# Scheme.net
KiCad netlist of a schematic drawn in EAGLE
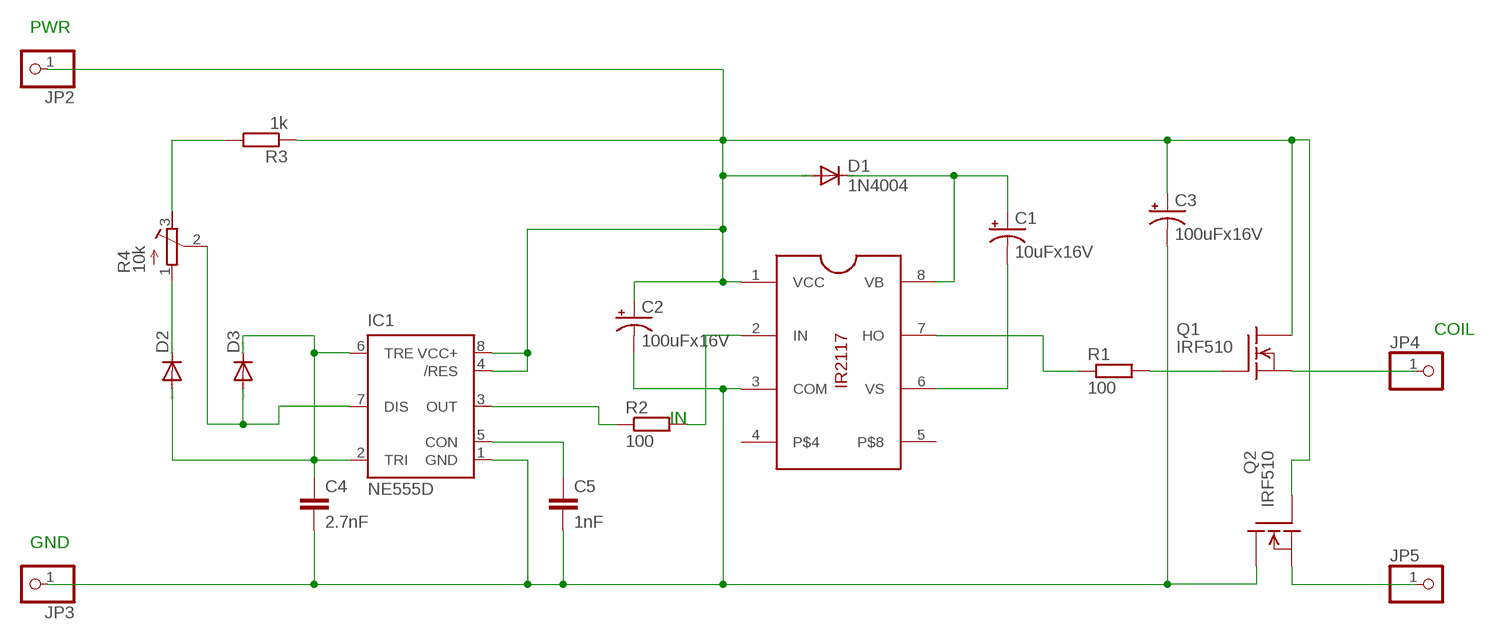
[diagram p0: schematic, sheet 1]

(export (version "E")
  (design (tool "Eeschema 10.0.6"))
  (components
    (comp (ref "C1")
      (value "10uFx16V")
      (footprint "eagle-import:SMC_D")
      (libsource (lib "eagle-import") (part "CPOL-USSMCD"))
    )
    (comp (ref "C2")
      (value "100uFx16V")
      (footprint "eagle-import:SMC_D")
      (libsource (lib "eagle-import") (part "CPOL-USSMCD"))
    )
    (comp (ref "C3")
      (value "100uFx16V")
      (footprint "eagle-import:SMC_D")
      (libsource (lib "eagle-import") (part "CPOL-USSMCD"))
    )
    (comp (ref "C4")
      (value "2.7nF")
      (footprint "eagle-import:C5B4.5")
      (libsource (lib "eagle-import") (part "C5/4.5"))
    )
    (comp (ref "C5")
      (value "1nF")
      (footprint "eagle-import:C5B4.5")
      (libsource (lib "eagle-import") (part "C5/4.5"))
    )
    (comp (ref "D1")
      (value "1N4004")
      (footprint "eagle-import:DO41-10")
      (libsource (lib "eagle-import") (part "1N4004"))
    )
    (comp (ref "D2")
      (value "DIODE-SOD106A-R")
      (footprint "eagle-import:SOD106A-R")
      (libsource (lib "eagle-import") (part "DIODE-SOD106A-R"))
    )
    (comp (ref "D3")
      (value "DIODE-SOD106A-R")
      (footprint "eagle-import:SOD106A-R")
      (libsource (lib "eagle-import") (part "DIODE-SOD106A-R"))
    )
    (comp (ref "IC1")
      (value "NE555D")
      (footprint "eagle-import:SO08")
      (libsource (lib "eagle-import") (part "NE555D"))
    )
    (comp (ref "JP2")
      (value "PINHD-1X1")
      (footprint "eagle-import:1X01")
      (libsource (lib "eagle-import") (part "PINHD-1X1"))
    )
    (comp (ref "JP3")
      (value "PINHD-1X1")
      (footprint "eagle-import:1X01")
      (libsource (lib "eagle-import") (part "PINHD-1X1"))
    )
    (comp (ref "JP4")
      (value "PINHD-1X1")
      (footprint "eagle-import:1X01")
      (libsource (lib "eagle-import") (part "PINHD-1X1"))
    )
    (comp (ref "JP5")
      (value "PINHD-1X1")
      (footprint "eagle-import:1X01")
      (libsource (lib "eagle-import") (part "PINHD-1X1"))
    )
    (comp (ref "Q1")
      (value "IRF510")
      (footprint "eagle-import:TO220")
      (libsource (lib "eagle-import") (part "IRF510"))
    )
    (comp (ref "Q2")
      (value "IRF510")
      (footprint "eagle-import:TO220")
      (libsource (lib "eagle-import") (part "IRF510"))
    )
    (comp (ref "R1")
      (value "100")
      (footprint "eagle-import:0207_15")
      (libsource (lib "eagle-import") (part "R-EU_0207/15"))
    )
    (comp (ref "R2")
      (value "100")
      (footprint "eagle-import:R1206")
      (libsource (lib "eagle-import") (part "R-EU_R1206"))
    )
    (comp (ref "R3")
      (value "1k")
      (footprint "eagle-import:0207_15")
      (libsource (lib "eagle-import") (part "R-EU_0207/15"))
    )
    (comp (ref "R4")
      (value "10k")
      (footprint "eagle-import:RTRIM3339P")
      (libsource (lib "eagle-import") (part "R-TRIMM3339P"))
    )
    (comp (ref "U$1")
      (value "IR2117SPBF")
      (footprint "eagle-import:SO8")
      (libsource (lib "eagle-import") (part "IR2117SPBF"))
    )
  )
  (nets
    (net (code "1") (name "Net-(IC1-CON)") (class "Default")
      (node (ref "C5") (pin "1") (pinfunction "1_1") (pintype "passive"))
      (node (ref "IC1") (pin "5") (pinfunction "CON_5") (pintype "input"))
    )
    (net (code "2") (name "Net-(IC1-DIS)") (class "Default")
      (node (ref "D3") (pin "A") (pinfunction "A_A") (pintype "passive"))
      (node (ref "IC1") (pin "7") (pinfunction "DIS_7") (pintype "input"))
      (node (ref "R4") (pin "2") (pinfunction "S_2") (pintype "passive"))
    )
    (net (code "3") (name "Net-(IC1-GND)") (class "Default")
      (node (ref "C2") (pin "-") (pinfunction "-_-") (pintype "passive"))
      (node (ref "C3") (pin "-") (pinfunction "-_-") (pintype "passive"))
      (node (ref "C4") (pin "2") (pinfunction "2_2") (pintype "passive"))
      (node (ref "C5") (pin "2") (pinfunction "2_2") (pintype "passive"))
      (node (ref "IC1") (pin "1") (pinfunction "GND_1") (pintype "power_in"))
      (node (ref "JP3") (pin "1") (pinfunction "1_1") (pintype "passive"))
      (node (ref "Q2") (pin "2") (pinfunction "D_2") (pintype "passive"))
      (node (ref "U$1") (pin "3") (pinfunction "COM_3") (pintype "bidirectional"))
    )
    (net (code "4") (name "Net-(IC1-OUT)") (class "Default")
      (node (ref "IC1") (pin "3") (pinfunction "OUT_3") (pintype "output"))
      (node (ref "R2") (pin "1") (pinfunction "1_1") (pintype "passive"))
    )
    (net (code "5") (name "Net-(IC1-TRE)") (class "Default")
      (node (ref "C4") (pin "1") (pinfunction "1_1") (pintype "passive"))
      (node (ref "D2") (pin "A") (pinfunction "A_A") (pintype "passive"))
      (node (ref "D3") (pin "C") (pinfunction "C_C") (pintype "passive"))
      (node (ref "IC1") (pin "2") (pinfunction "TRI_2") (pintype "input"))
      (node (ref "IC1") (pin "6") (pinfunction "TRE_6") (pintype "input"))
    )
    (net (code "6") (name "Net-(IC1-VCC+)") (class "Default")
      (node (ref "C2") (pin "+") (pinfunction "+_+") (pintype "passive"))
      (node (ref "C3") (pin "+") (pinfunction "+_+") (pintype "passive"))
      (node (ref "D1") (pin "A") (pinfunction "A_A") (pintype "passive"))
      (node (ref "IC1") (pin "4") (pinfunction "/RES_4") (pintype "input"))
      (node (ref "IC1") (pin "8") (pinfunction "VCC+_8") (pintype "power_in"))
      (node (ref "JP2") (pin "1") (pinfunction "1_1") (pintype "passive"))
      (node (ref "Q1") (pin "2") (pinfunction "D_2") (pintype "passive"))
      (node (ref "Q2") (pin "1") (pinfunction "G_1") (pintype "passive"))
      (node (ref "R3") (pin "1") (pinfunction "1_1") (pintype "passive"))
      (node (ref "U$1") (pin "1") (pinfunction "VCC_1") (pintype "bidirectional"))
    )
    (net (code "7") (name "Net-(Q1-G)") (class "Default")
      (node (ref "Q1") (pin "1") (pinfunction "G_1") (pintype "passive"))
      (node (ref "R1") (pin "2") (pinfunction "2_2") (pintype "passive"))
    )
    (net (code "8") (name "Net-(Q1-S)") (class "Default")
      (node (ref "JP4") (pin "1") (pinfunction "1_1") (pintype "passive"))
      (node (ref "Q1") (pin "3") (pinfunction "S_3") (pintype "passive"))
    )
    (net (code "9") (name "Net-(Q2-S)") (class "Default")
      (node (ref "JP5") (pin "1") (pinfunction "1_1") (pintype "passive"))
      (node (ref "Q2") (pin "3") (pinfunction "S_3") (pintype "passive"))
    )
    (net (code "10") (name "Net-(R4-A)") (class "Default")
      (node (ref "D2") (pin "C") (pinfunction "C_C") (pintype "passive"))
      (node (ref "R4") (pin "1") (pinfunction "A_1") (pintype "passive"))
    )
    (net (code "11") (name "Net-(R4-E)") (class "Default")
      (node (ref "R3") (pin "2") (pinfunction "2_2") (pintype "passive"))
      (node (ref "R4") (pin "3") (pinfunction "E_3") (pintype "passive"))
    )
    (net (code "12") (name "Net-(U$1-HO)") (class "Default")
      (node (ref "R1") (pin "1") (pinfunction "1_1") (pintype "passive"))
      (node (ref "U$1") (pin "7") (pinfunction "HO_7") (pintype "bidirectional"))
    )
    (net (code "13") (name "Net-(U$1-IN)") (class "Default")
      (node (ref "R2") (pin "2") (pinfunction "2_2") (pintype "passive"))
      (node (ref "U$1") (pin "2") (pinfunction "IN_2") (pintype "bidirectional"))
    )
    (net (code "14") (name "Net-(U$1-VB)") (class "Default")
      (node (ref "C1") (pin "+") (pinfunction "+_+") (pintype "passive"))
      (node (ref "D1") (pin "C") (pinfunction "C_C") (pintype "passive"))
      (node (ref "U$1") (pin "8") (pinfunction "VB_8") (pintype "bidirectional"))
    )
    (net (code "15") (name "Net-(U$1-VS)") (class "Default")
      (node (ref "C1") (pin "-") (pinfunction "-_-") (pintype "passive"))
      (node (ref "U$1") (pin "6") (pinfunction "VS_6") (pintype "bidirectional"))
    )
    (net (code "16") (name "unconnected-(U$1-P$4-Pad4)") (class "Default")
      (node (ref "U$1") (pin "4") (pinfunction "P$4_4") (pintype "bidirectional"))
    )
    (net (code "17") (name "unconnected-(U$1-P$8-Pad5)") (class "Default")
      (node (ref "U$1") (pin "5") (pinfunction "P$8_5") (pintype "bidirectional"))
    )
  )
)
